# 3_RK3399_PMU.net
KiCad netlist of a schematic drawn in Altium Designer
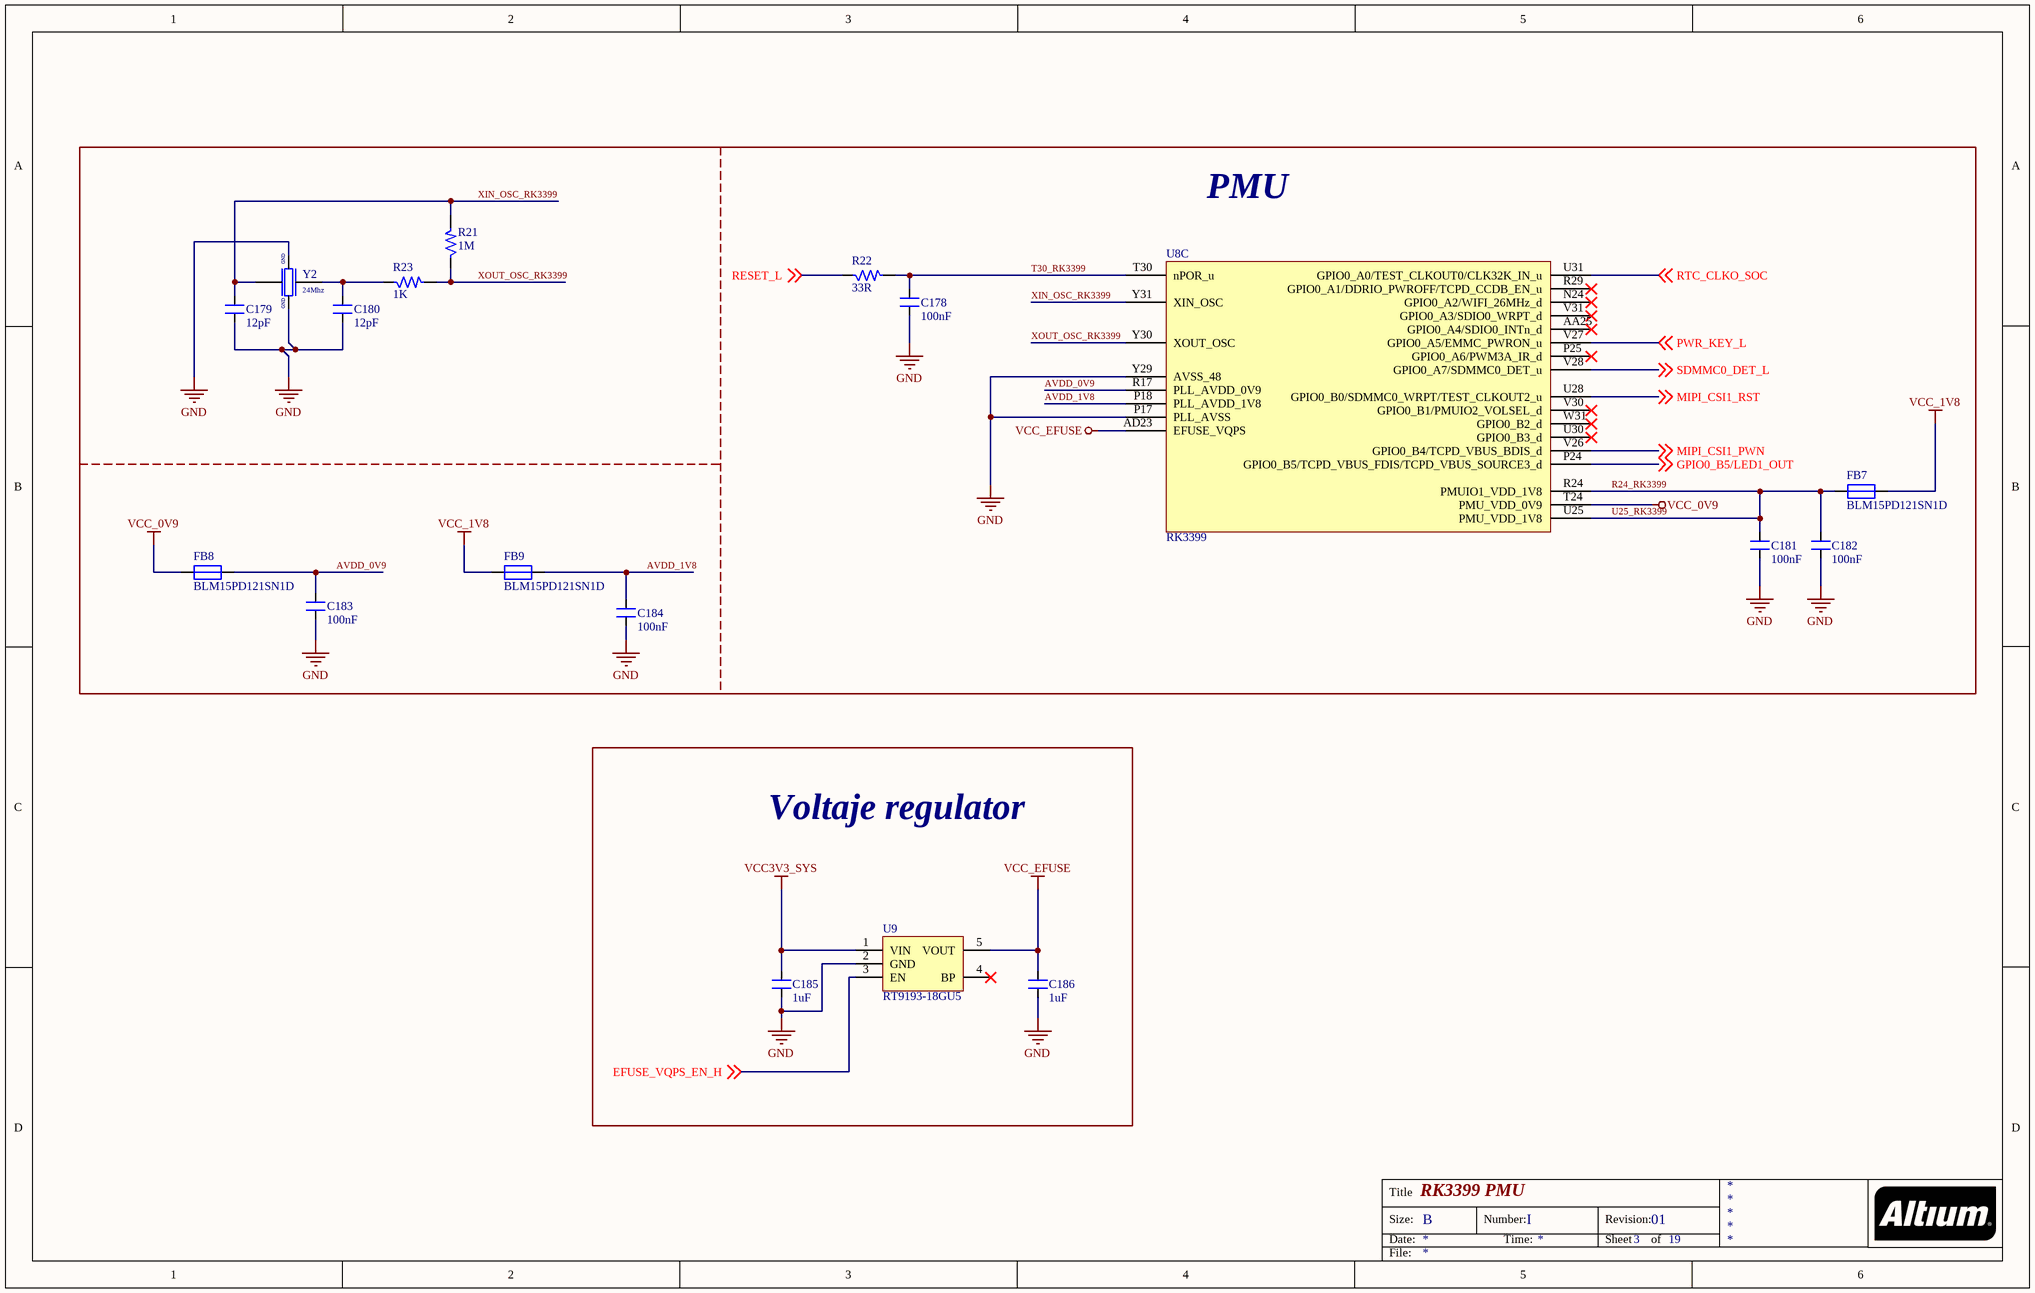
[diagram p0: [3] RK3399_PMU.SchDoc]

(export (version "E")
  (design (tool "Eeschema 10.0.6"))
  (components
    (comp (ref "C178")
      (value "100nF")
      (footprint "CAP_0201")
      (description "0.1µF ±10% 25V Ceramic Capacitor X5R 0201 (0603 Metric)")
      (fields
        (field (name "MANUFACTURER") "TDK Corporation")
        (field (name "MANUFACTURER PART NUMBER") "C0603X5R1E104K030BB")
      )
      (libsource (lib "EsteemPCB_SOM_Course_intlib") (part "CAP_100nF-25V-10%-0201"))
    )
    (comp (ref "C179")
      (value "12pF")
      (footprint "CAP_0201")
      (description "12pF ±10% 16V Ceramic Capacitor C0G, NP0 0201 (0603 Metric)")
      (fields
        (field (name "MANUFACTURER") "AVX Corporation")
        (field (name "MANUFACTURER PART NUMBER") "0201YA120KAT2A")
      )
      (libsource (lib "EsteemPCB_SOM_Course_intlib") (part "CAP_12pF-16V-10%-0201"))
    )
    (comp (ref "C180")
      (value "12pF")
      (footprint "CAP_0201")
      (description "12pF ±10% 16V Ceramic Capacitor C0G, NP0 0201 (0603 Metric)")
      (fields
        (field (name "MANUFACTURER") "AVX Corporation")
        (field (name "MANUFACTURER PART NUMBER") "0201YA120KAT2A")
      )
      (libsource (lib "EsteemPCB_SOM_Course_intlib") (part "CAP_12pF-16V-10%-0201"))
    )
    (comp (ref "C181")
      (value "100nF")
      (footprint "CAP_0201")
      (description "0.1µF ±10% 25V Ceramic Capacitor X5R 0201 (0603 Metric)")
      (fields
        (field (name "MANUFACTURER") "TDK Corporation")
        (field (name "MANUFACTURER PART NUMBER") "C0603X5R1E104K030BB")
      )
      (libsource (lib "EsteemPCB_SOM_Course_intlib") (part "CAP_100nF-25V-10%-0201"))
    )
    (comp (ref "C182")
      (value "100nF")
      (footprint "CAP_0201")
      (description "0.1µF ±10% 25V Ceramic Capacitor X5R 0201 (0603 Metric)")
      (fields
        (field (name "MANUFACTURER") "TDK Corporation")
        (field (name "MANUFACTURER PART NUMBER") "C0603X5R1E104K030BB")
      )
      (libsource (lib "EsteemPCB_SOM_Course_intlib") (part "CAP_100nF-25V-10%-0201"))
    )
    (comp (ref "C183")
      (value "100nF")
      (footprint "CAP_0201")
      (description "0.1µF ±10% 25V Ceramic Capacitor X5R 0201 (0603 Metric)")
      (fields
        (field (name "MANUFACTURER") "TDK Corporation")
        (field (name "MANUFACTURER PART NUMBER") "C0603X5R1E104K030BB")
      )
      (libsource (lib "EsteemPCB_SOM_Course_intlib") (part "CAP_100nF-25V-10%-0201"))
    )
    (comp (ref "C184")
      (value "100nF")
      (footprint "CAP_0201")
      (description "0.1µF ±10% 25V Ceramic Capacitor X5R 0201 (0603 Metric)")
      (fields
        (field (name "MANUFACTURER") "TDK Corporation")
        (field (name "MANUFACTURER PART NUMBER") "C0603X5R1E104K030BB")
      )
      (libsource (lib "EsteemPCB_SOM_Course_intlib") (part "CAP_100nF-25V-10%-0201"))
    )
    (comp (ref "C185")
      (value "1uF")
      (footprint "CAP_0201")
      (description "1µF ±20% 16V Ceramic Capacitor X5R 0201 (0603 Metric)")
      (fields
        (field (name "MANUFACTURER") "Samsung Electro-Mechanics")
        (field (name "MANUFACTURER PART NUMBER") "CL03A105MO3NRNH")
      )
      (libsource (lib "EsteemPCB_SOM_Course_intlib") (part "CAP_1uF-16V-10%-0201"))
    )
    (comp (ref "C186")
      (value "1uF")
      (footprint "CAP_0201")
      (description "1µF ±20% 16V Ceramic Capacitor X5R 0201 (0603 Metric)")
      (fields
        (field (name "MANUFACTURER") "Samsung Electro-Mechanics")
        (field (name "MANUFACTURER PART NUMBER") "CL03A105MO3NRNH")
      )
      (libsource (lib "EsteemPCB_SOM_Course_intlib") (part "CAP_1uF-16V-10%-0201"))
    )
    (comp (ref "FB7")
      (value "BLM15PD121SN1D")
      (footprint "RES_0402")
      (description "120 Ohms @ 100MHz 1 Power Line Ferrite Bead 0402 (1005 Metric) 1.3A 90mOhm")
      (fields (field (name "MANUFACTURER") "Murata Electronics"))
      (libsource (lib "EsteemPCB_SOM_Course_intlib") (part "FB_120R-1.3A-100Mhz-0402"))
    )
    (comp (ref "FB8")
      (value "BLM15PD121SN1D")
      (footprint "RES_0402")
      (description "120 Ohms @ 100MHz 1 Power Line Ferrite Bead 0402 (1005 Metric) 1.3A 90mOhm")
      (fields (field (name "MANUFACTURER") "Murata Electronics"))
      (libsource (lib "EsteemPCB_SOM_Course_intlib") (part "FB_120R-1.3A-100Mhz-0402"))
    )
    (comp (ref "FB9")
      (value "BLM15PD121SN1D")
      (footprint "RES_0402")
      (description "120 Ohms @ 100MHz 1 Power Line Ferrite Bead 0402 (1005 Metric) 1.3A 90mOhm")
      (fields (field (name "MANUFACTURER") "Murata Electronics"))
      (libsource (lib "EsteemPCB_SOM_Course_intlib") (part "FB_120R-1.3A-100Mhz-0402"))
    )
    (comp (ref "R21")
      (value "1M")
      (footprint "RES_0201")
      (description "1 MOhms ±1% 0.05W, 1/20W Chip Resistor 0201 (0603 Metric) Thick Film")
      (fields
        (field (name "MANUFACTURER") "Yageo")
        (field (name "MANUFACTURER PART NUMBER") "RC0201FR-071ML")
      )
      (libsource (lib "EsteemPCB_SOM_Course_intlib") (part "RES_1M-0.05W-1%-0201"))
    )
    (comp (ref "R22")
      (value "33R")
      (footprint "RES_0201")
      (description "33 Ohms ±1% 0.05W, 1/20W Chip Resistor 0201 (0603 Metric) Thick Film")
      (fields
        (field (name "MANUFACTURER") "Yageo")
        (field (name "MANUFACTURER PART NUMBER") "RC0201FR-0733RL")
      )
      (libsource (lib "EsteemPCB_SOM_Course_intlib") (part "RES_33R-0.05W-1%-0201"))
    )
    (comp (ref "R23")
      (value "1K")
      (footprint "RES_0201")
      (description "1 kOhms ±1% 0.05W, 1/20W Chip Resistor 0201 (0603 Metric) Thick Film")
      (fields
        (field (name "MANUFACTURER") "Yageo")
        (field (name "MANUFACTURER PART NUMBER") "RC0201FR-071KL")
      )
      (libsource (lib "EsteemPCB_SOM_Course_intlib") (part "RES_1K-0.05W-1%-0201"))
    )
    (comp (ref "U8")
      (value "RK3399")
      (footprint "FBGA828_23_826X826")
      (description "RK3399 is a low power, high performance processor for computing, personal mobile.")
      (fields (field (name "MANUFACTURER") "Rockchip"))
      (libsource (lib "EsteemPCB_SOM_Course_intlib") (part "IC_RK3399-FCBGA828"))
    )
    (comp (ref "U9")
      (value "RT9193-18GU5")
      (footprint "SC70-5")
      (description "Linear Voltage Regulator IC 1 Output 300mA SC-70-5")
      (fields (field (name "MANUFACTURER") "Richtek USA Inc."))
      (libsource (lib "EsteemPCB_SOM_Course_intlib") (part "REG_1.8V-300mA-5.5V-SC70-5"))
    )
    (comp (ref "Y2")
      (value "24Mhz")
      (footprint "XTAL_ABM8AIG-24.000MHZ-12-2Z-T3")
      (description "24MHz ±20ppm Crystal 12pF 50 Ohms 4-SMD, No Lead")
      (fields
        (field (name "MANUFACTURER") "Abracon LLC")
        (field (name "MANUFACTURER PART NUMBER") "ABM8AIG-24.000MHZ-12-2Z-T3")
      )
      (libsource (lib "EsteemPCB_SOM_Course_intlib") (part "XTAL_24Mhz-12pF-4-SMD"))
    )
  )
  (nets
    (net (code "1") (name "/AVDD_0V9") (class "Default")
      (node (ref "C183") (pin "2") (pinfunction "2_2") (pintype "passive"))
      (node (ref "FB8") (pin "2") (pinfunction "2_2") (pintype "passive"))
      (node (ref "U8") (pin "R17") (pinfunction "PLL_AVDD_0V9_R17") (pintype "passive"))
    )
    (net (code "2") (name "/AVDD_1V8") (class "Default")
      (node (ref "C184") (pin "2") (pinfunction "2_2") (pintype "passive"))
      (node (ref "FB9") (pin "2") (pinfunction "2_2") (pintype "passive"))
      (node (ref "U8") (pin "P18") (pinfunction "PLL_AVDD_1V8_P18") (pintype "passive"))
    )
    (net (code "3") (name "/R24_RK3399") (class "Default")
      (node (ref "C181") (pin "2") (pinfunction "2_2") (pintype "passive"))
      (node (ref "C182") (pin "2") (pinfunction "2_2") (pintype "passive"))
      (node (ref "FB7") (pin "1") (pinfunction "1_1") (pintype "passive"))
      (node (ref "U8") (pin "R24") (pinfunction "PMUIO1_VDD_1V8_R24") (pintype "passive"))
      (node (ref "U8") (pin "U25") (pinfunction "PMU_VDD_1V8_U25") (pintype "passive"))
    )
    (net (code "4") (name "/T30_RK3399") (class "Default")
      (node (ref "C178") (pin "2") (pinfunction "2_2") (pintype "passive"))
      (node (ref "R22") (pin "2") (pinfunction "2_2") (pintype "passive"))
      (node (ref "U8") (pin "T30") (pinfunction "nPOR_u_T30") (pintype "passive"))
    )
    (net (code "5") (name "/XIN_OSC_RK3399") (class "Default")
      (node (ref "C179") (pin "2") (pinfunction "2_2") (pintype "passive"))
      (node (ref "R21") (pin "2") (pinfunction "2_2") (pintype "passive"))
      (node (ref "U8") (pin "Y31") (pinfunction "XIN_OSC_Y31") (pintype "passive"))
      (node (ref "Y2") (pin "1") (pinfunction "1_1") (pintype "passive"))
    )
    (net (code "6") (name "/XOUT_OSC_RK3399") (class "Default")
      (node (ref "R21") (pin "1") (pinfunction "1_1") (pintype "passive"))
      (node (ref "R23") (pin "2") (pinfunction "2_2") (pintype "passive"))
      (node (ref "U8") (pin "Y30") (pinfunction "XOUT_OSC_Y30") (pintype "passive"))
    )
    (net (code "7") (name "EFUSE_VQPS_EN_H") (class "Default")
      (node (ref "U9") (pin "3") (pinfunction "EN_3") (pintype "passive"))
    )
    (net (code "8") (name "GND") (class "Default")
      (node (ref "C178") (pin "1") (pinfunction "1_1") (pintype "passive"))
      (node (ref "C179") (pin "1") (pinfunction "1_1") (pintype "passive"))
      (node (ref "C180") (pin "1") (pinfunction "1_1") (pintype "passive"))
      (node (ref "C181") (pin "1") (pinfunction "1_1") (pintype "passive"))
      (node (ref "C182") (pin "1") (pinfunction "1_1") (pintype "passive"))
      (node (ref "C183") (pin "1") (pinfunction "1_1") (pintype "passive"))
      (node (ref "C184") (pin "1") (pinfunction "1_1") (pintype "passive"))
      (node (ref "C185") (pin "1") (pinfunction "1_1") (pintype "passive"))
      (node (ref "C186") (pin "1") (pinfunction "1_1") (pintype "passive"))
      (node (ref "U8") (pin "P17") (pinfunction "PLL_AVSS_P17") (pintype "passive"))
      (node (ref "U8") (pin "Y29") (pinfunction "AVSS_48_Y29") (pintype "passive"))
      (node (ref "U9") (pin "2") (pinfunction "GND_2") (pintype "passive"))
      (node (ref "Y2") (pin "2") (pinfunction "2_2") (pintype "passive"))
      (node (ref "Y2") (pin "4") (pinfunction "4_4") (pintype "passive"))
    )
    (net (code "9") (name "GPIO0_B5{slash}LED1_OUT") (class "Default")
      (node (ref "U8") (pin "P24") (pinfunction "GPIO0_B5/TCPD_VBUS_FDIS/TCPD_VBUS_SOURCE3_d_P24") (pintype "passive"))
    )
    (net (code "10") (name "MIPI_CSI1_PWN") (class "Default")
      (node (ref "U8") (pin "V26") (pinfunction "GPIO0_B4/TCPD_VBUS_BDIS_d_V26") (pintype "passive"))
    )
    (net (code "11") (name "MIPI_CSI1_RST") (class "Default")
      (node (ref "U8") (pin "U28") (pinfunction "GPIO0_B0/SDMMC0_WRPT/TEST_CLKOUT2_u_U28") (pintype "passive"))
    )
    (net (code "12") (name "Net-(C180-Pad2)") (class "Default")
      (node (ref "C180") (pin "2") (pinfunction "2_2") (pintype "passive"))
      (node (ref "R23") (pin "1") (pinfunction "1_1") (pintype "passive"))
      (node (ref "Y2") (pin "3") (pinfunction "3_3") (pintype "passive"))
    )
    (net (code "13") (name "PWR_KEY_L") (class "Default")
      (node (ref "U8") (pin "V27") (pinfunction "GPIO0_A5/EMMC_PWRON_u_V27") (pintype "passive"))
    )
    (net (code "14") (name "RESET_L") (class "Default")
      (node (ref "R22") (pin "1") (pinfunction "1_1") (pintype "passive"))
    )
    (net (code "15") (name "RTC_CLKO_SOC") (class "Default")
      (node (ref "U8") (pin "U31") (pinfunction "GPIO0_A0/TEST_CLKOUT0/CLK32K_IN_u_U31") (pintype "passive"))
    )
    (net (code "16") (name "SDMMC0_DET_L") (class "Default")
      (node (ref "U8") (pin "V28") (pinfunction "GPIO0_A7/SDMMC0_DET_u_V28") (pintype "passive"))
    )
    (net (code "17") (name "VCC3V3_SYS") (class "Default")
      (node (ref "C185") (pin "2") (pinfunction "2_2") (pintype "passive"))
      (node (ref "U9") (pin "1") (pinfunction "VIN_1") (pintype "passive"))
    )
    (net (code "18") (name "VCC_0V9") (class "Default")
      (node (ref "FB8") (pin "1") (pinfunction "1_1") (pintype "passive"))
      (node (ref "U8") (pin "T24") (pinfunction "PMU_VDD_0V9_T24") (pintype "passive"))
    )
    (net (code "19") (name "VCC_1V8") (class "Default")
      (node (ref "FB7") (pin "2") (pinfunction "2_2") (pintype "passive"))
      (node (ref "FB9") (pin "1") (pinfunction "1_1") (pintype "passive"))
    )
    (net (code "20") (name "VCC_EFUSE") (class "Default")
      (node (ref "C186") (pin "2") (pinfunction "2_2") (pintype "passive"))
      (node (ref "U8") (pin "AD23") (pinfunction "EFUSE_VQPS_AD23") (pintype "passive"))
      (node (ref "U9") (pin "5") (pinfunction "VOUT_5") (pintype "passive"))
    )
    (net (code "21") (name "unconnected-(U8C-GPIO0_A1{slash}DDRIO_PWROFF{slash}TCPD_CCDB_EN_u-PadR29)") (class "Default")
      (node (ref "U8") (pin "R29") (pinfunction "GPIO0_A1/DDRIO_PWROFF/TCPD_CCDB_EN_u_R29") (pintype "passive+no_connect"))
    )
    (net (code "22") (name "unconnected-(U8C-GPIO0_A2{slash}WIFI_26MHz_d-PadN24)") (class "Default")
      (node (ref "U8") (pin "N24") (pinfunction "GPIO0_A2/WIFI_26MHz_d_N24") (pintype "passive+no_connect"))
    )
    (net (code "23") (name "unconnected-(U8C-GPIO0_A3{slash}SDIO0_WRPT_d-PadV31)") (class "Default")
      (node (ref "U8") (pin "V31") (pinfunction "GPIO0_A3/SDIO0_WRPT_d_V31") (pintype "passive+no_connect"))
    )
    (net (code "24") (name "unconnected-(U8C-GPIO0_A4{slash}SDIO0_INTn_d-PadAA25)") (class "Default")
      (node (ref "U8") (pin "AA25") (pinfunction "GPIO0_A4/SDIO0_INTn_d_AA25") (pintype "passive+no_connect"))
    )
    (net (code "25") (name "unconnected-(U8C-GPIO0_A6{slash}PWM3A_IR_d-PadP25)") (class "Default")
      (node (ref "U8") (pin "P25") (pinfunction "GPIO0_A6/PWM3A_IR_d_P25") (pintype "passive+no_connect"))
    )
    (net (code "26") (name "unconnected-(U8C-GPIO0_B1{slash}PMUIO2_VOLSEL_d-PadV30)") (class "Default")
      (node (ref "U8") (pin "V30") (pinfunction "GPIO0_B1/PMUIO2_VOLSEL_d_V30") (pintype "passive+no_connect"))
    )
    (net (code "27") (name "unconnected-(U8C-GPIO0_B2_d-PadW31)") (class "Default")
      (node (ref "U8") (pin "W31") (pinfunction "GPIO0_B2_d_W31") (pintype "passive+no_connect"))
    )
    (net (code "28") (name "unconnected-(U8C-GPIO0_B3_d-PadU30)") (class "Default")
      (node (ref "U8") (pin "U30") (pinfunction "GPIO0_B3_d_U30") (pintype "passive+no_connect"))
    )
    (net (code "29") (name "unconnected-(U9-BP-Pad4)") (class "Default")
      (node (ref "U9") (pin "4") (pinfunction "BP_4") (pintype "passive+no_connect"))
    )
  )
)
